# dcdc.net
KiCad netlist of a schematic drawn in EAGLE
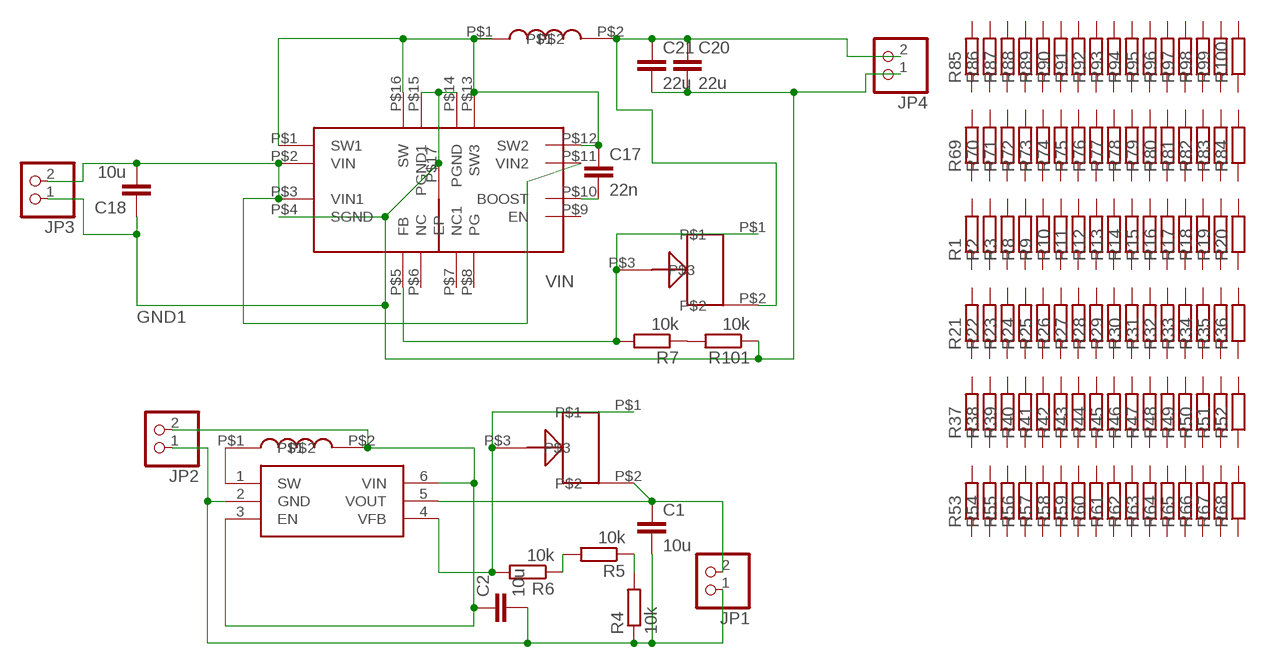
[diagram p0: schematic, sheet 1]

(export (version "E")
  (design (tool "Eeschema 10.0.6"))
  (components
    (comp (ref "C1")
      (value "10u")
      (footprint "eagle-import:C1206K")
      (libsource (lib "eagle-import") (part "C-EUC1206K"))
    )
    (comp (ref "C2")
      (value "10u")
      (footprint "eagle-import:C1206K")
      (libsource (lib "eagle-import") (part "C-EUC1206K"))
    )
    (comp (ref "C17")
      (value "22n")
      (footprint "eagle-import:C0603")
      (libsource (lib "eagle-import") (part "C-EUC0603"))
    )
    (comp (ref "C18")
      (value "10u")
      (footprint "eagle-import:C1206K")
      (libsource (lib "eagle-import") (part "C-EUC1206K"))
    )
    (comp (ref "C20")
      (value "22u")
      (footprint "eagle-import:C1206K")
      (libsource (lib "eagle-import") (part "C-EUC1206K"))
    )
    (comp (ref "C21")
      (value "22u")
      (footprint "eagle-import:C1206K")
      (libsource (lib "eagle-import") (part "C-EUC1206K"))
    )
    (comp (ref "JP1")
      (value "PINHD-1X2")
      (footprint "eagle-import:1X02")
      (libsource (lib "eagle-import") (part "PINHD-1X2"))
    )
    (comp (ref "JP2")
      (value "PINHD-1X2")
      (footprint "eagle-import:1X02")
      (libsource (lib "eagle-import") (part "PINHD-1X2"))
    )
    (comp (ref "JP3")
      (value "PINHD-1X2")
      (footprint "eagle-import:1X02")
      (libsource (lib "eagle-import") (part "PINHD-1X2"))
    )
    (comp (ref "JP4")
      (value "PINHD-1X2")
      (footprint "eagle-import:1X02")
      (libsource (lib "eagle-import") (part "PINHD-1X2"))
    )
    (comp (ref "R1")
      (value "R-EU_R0402")
      (footprint "eagle-import:R0402")
      (libsource (lib "eagle-import") (part "R-EU_R0402"))
    )
    (comp (ref "R2")
      (value "R-EU_R0402")
      (footprint "eagle-import:R0402")
      (libsource (lib "eagle-import") (part "R-EU_R0402"))
    )
    (comp (ref "R3")
      (value "R-EU_R0402")
      (footprint "eagle-import:R0402")
      (libsource (lib "eagle-import") (part "R-EU_R0402"))
    )
    (comp (ref "R4")
      (value "10k")
      (footprint "eagle-import:R0603")
      (libsource (lib "eagle-import") (part "R-EU_R0603"))
    )
    (comp (ref "R5")
      (value "10k")
      (footprint "eagle-import:R0603")
      (libsource (lib "eagle-import") (part "R-EU_R0603"))
    )
    (comp (ref "R6")
      (value "10k")
      (footprint "eagle-import:R0603")
      (libsource (lib "eagle-import") (part "R-EU_R0603"))
    )
    (comp (ref "R7")
      (value "10k")
      (footprint "eagle-import:R0603")
      (libsource (lib "eagle-import") (part "R-EU_R0603"))
    )
    (comp (ref "R8")
      (value "R-EU_R0402")
      (footprint "eagle-import:R0402")
      (libsource (lib "eagle-import") (part "R-EU_R0402"))
    )
    (comp (ref "R9")
      (value "R-EU_R0402")
      (footprint "eagle-import:R0402")
      (libsource (lib "eagle-import") (part "R-EU_R0402"))
    )
    (comp (ref "R10")
      (value "R-EU_R0402")
      (footprint "eagle-import:R0402")
      (libsource (lib "eagle-import") (part "R-EU_R0402"))
    )
    (comp (ref "R11")
      (value "R-EU_R0402")
      (footprint "eagle-import:R0402")
      (libsource (lib "eagle-import") (part "R-EU_R0402"))
    )
    (comp (ref "R12")
      (value "R-EU_R0402")
      (footprint "eagle-import:R0402")
      (libsource (lib "eagle-import") (part "R-EU_R0402"))
    )
    (comp (ref "R13")
      (value "R-EU_R0402")
      (footprint "eagle-import:R0402")
      (libsource (lib "eagle-import") (part "R-EU_R0402"))
    )
    (comp (ref "R14")
      (value "R-EU_R0402")
      (footprint "eagle-import:R0402")
      (libsource (lib "eagle-import") (part "R-EU_R0402"))
    )
    (comp (ref "R15")
      (value "R-EU_R0402")
      (footprint "eagle-import:R0402")
      (libsource (lib "eagle-import") (part "R-EU_R0402"))
    )
    (comp (ref "R16")
      (value "R-EU_R0402")
      (footprint "eagle-import:R0402")
      (libsource (lib "eagle-import") (part "R-EU_R0402"))
    )
    (comp (ref "R17")
      (value "R-EU_R0402")
      (footprint "eagle-import:R0402")
      (libsource (lib "eagle-import") (part "R-EU_R0402"))
    )
    (comp (ref "R18")
      (value "R-EU_R0402")
      (footprint "eagle-import:R0402")
      (libsource (lib "eagle-import") (part "R-EU_R0402"))
    )
    (comp (ref "R19")
      (value "R-EU_R0402")
      (footprint "eagle-import:R0402")
      (libsource (lib "eagle-import") (part "R-EU_R0402"))
    )
    (comp (ref "R20")
      (value "R-EU_R0402")
      (footprint "eagle-import:R0402")
      (libsource (lib "eagle-import") (part "R-EU_R0402"))
    )
    (comp (ref "R21")
      (value "R-EU_R0402")
      (footprint "eagle-import:R0402")
      (libsource (lib "eagle-import") (part "R-EU_R0402"))
    )
    (comp (ref "R22")
      (value "R-EU_R0402")
      (footprint "eagle-import:R0402")
      (libsource (lib "eagle-import") (part "R-EU_R0402"))
    )
    (comp (ref "R23")
      (value "R-EU_R0402")
      (footprint "eagle-import:R0402")
      (libsource (lib "eagle-import") (part "R-EU_R0402"))
    )
    (comp (ref "R24")
      (value "R-EU_R0402")
      (footprint "eagle-import:R0402")
      (libsource (lib "eagle-import") (part "R-EU_R0402"))
    )
    (comp (ref "R25")
      (value "R-EU_R0402")
      (footprint "eagle-import:R0402")
      (libsource (lib "eagle-import") (part "R-EU_R0402"))
    )
    (comp (ref "R26")
      (value "R-EU_R0402")
      (footprint "eagle-import:R0402")
      (libsource (lib "eagle-import") (part "R-EU_R0402"))
    )
    (comp (ref "R27")
      (value "R-EU_R0402")
      (footprint "eagle-import:R0402")
      (libsource (lib "eagle-import") (part "R-EU_R0402"))
    )
    (comp (ref "R28")
      (value "R-EU_R0402")
      (footprint "eagle-import:R0402")
      (libsource (lib "eagle-import") (part "R-EU_R0402"))
    )
    (comp (ref "R29")
      (value "R-EU_R0402")
      (footprint "eagle-import:R0402")
      (libsource (lib "eagle-import") (part "R-EU_R0402"))
    )
    (comp (ref "R30")
      (value "R-EU_R0402")
      (footprint "eagle-import:R0402")
      (libsource (lib "eagle-import") (part "R-EU_R0402"))
    )
    (comp (ref "R31")
      (value "R-EU_R0402")
      (footprint "eagle-import:R0402")
      (libsource (lib "eagle-import") (part "R-EU_R0402"))
    )
    (comp (ref "R32")
      (value "R-EU_R0402")
      (footprint "eagle-import:R0402")
      (libsource (lib "eagle-import") (part "R-EU_R0402"))
    )
    (comp (ref "R33")
      (value "R-EU_R0402")
      (footprint "eagle-import:R0402")
      (libsource (lib "eagle-import") (part "R-EU_R0402"))
    )
    (comp (ref "R34")
      (value "R-EU_R0402")
      (footprint "eagle-import:R0402")
      (libsource (lib "eagle-import") (part "R-EU_R0402"))
    )
    (comp (ref "R35")
      (value "R-EU_R0402")
      (footprint "eagle-import:R0402")
      (libsource (lib "eagle-import") (part "R-EU_R0402"))
    )
    (comp (ref "R36")
      (value "R-EU_R0402")
      (footprint "eagle-import:R0402")
      (libsource (lib "eagle-import") (part "R-EU_R0402"))
    )
    (comp (ref "R37")
      (value "R-EU_R0603")
      (footprint "eagle-import:R0603")
      (libsource (lib "eagle-import") (part "R-EU_R0603"))
    )
    (comp (ref "R38")
      (value "R-EU_R0603")
      (footprint "eagle-import:R0603")
      (libsource (lib "eagle-import") (part "R-EU_R0603"))
    )
    (comp (ref "R39")
      (value "R-EU_R0603")
      (footprint "eagle-import:R0603")
      (libsource (lib "eagle-import") (part "R-EU_R0603"))
    )
    (comp (ref "R40")
      (value "R-EU_R0603")
      (footprint "eagle-import:R0603")
      (libsource (lib "eagle-import") (part "R-EU_R0603"))
    )
    (comp (ref "R41")
      (value "R-EU_R0603")
      (footprint "eagle-import:R0603")
      (libsource (lib "eagle-import") (part "R-EU_R0603"))
    )
    (comp (ref "R42")
      (value "R-EU_R0603")
      (footprint "eagle-import:R0603")
      (libsource (lib "eagle-import") (part "R-EU_R0603"))
    )
    (comp (ref "R43")
      (value "R-EU_R0603")
      (footprint "eagle-import:R0603")
      (libsource (lib "eagle-import") (part "R-EU_R0603"))
    )
    (comp (ref "R44")
      (value "R-EU_R0603")
      (footprint "eagle-import:R0603")
      (libsource (lib "eagle-import") (part "R-EU_R0603"))
    )
    (comp (ref "R45")
      (value "R-EU_R0603")
      (footprint "eagle-import:R0603")
      (libsource (lib "eagle-import") (part "R-EU_R0603"))
    )
    (comp (ref "R46")
      (value "R-EU_R0603")
      (footprint "eagle-import:R0603")
      (libsource (lib "eagle-import") (part "R-EU_R0603"))
    )
    (comp (ref "R47")
      (value "R-EU_R0603")
      (footprint "eagle-import:R0603")
      (libsource (lib "eagle-import") (part "R-EU_R0603"))
    )
    (comp (ref "R48")
      (value "R-EU_R0603")
      (footprint "eagle-import:R0603")
      (libsource (lib "eagle-import") (part "R-EU_R0603"))
    )
    (comp (ref "R49")
      (value "R-EU_R0603")
      (footprint "eagle-import:R0603")
      (libsource (lib "eagle-import") (part "R-EU_R0603"))
    )
    (comp (ref "R50")
      (value "R-EU_R0603")
      (footprint "eagle-import:R0603")
      (libsource (lib "eagle-import") (part "R-EU_R0603"))
    )
    (comp (ref "R51")
      (value "R-EU_R0603")
      (footprint "eagle-import:R0603")
      (libsource (lib "eagle-import") (part "R-EU_R0603"))
    )
    (comp (ref "R52")
      (value "R-EU_R0603")
      (footprint "eagle-import:R0603")
      (libsource (lib "eagle-import") (part "R-EU_R0603"))
    )
    (comp (ref "R53")
      (value "R-EU_R0603")
      (footprint "eagle-import:R0603")
      (libsource (lib "eagle-import") (part "R-EU_R0603"))
    )
    (comp (ref "R54")
      (value "R-EU_R0603")
      (footprint "eagle-import:R0603")
      (libsource (lib "eagle-import") (part "R-EU_R0603"))
    )
    (comp (ref "R55")
      (value "R-EU_R0603")
      (footprint "eagle-import:R0603")
      (libsource (lib "eagle-import") (part "R-EU_R0603"))
    )
    (comp (ref "R56")
      (value "R-EU_R0603")
      (footprint "eagle-import:R0603")
      (libsource (lib "eagle-import") (part "R-EU_R0603"))
    )
    (comp (ref "R57")
      (value "R-EU_R0603")
      (footprint "eagle-import:R0603")
      (libsource (lib "eagle-import") (part "R-EU_R0603"))
    )
    (comp (ref "R58")
      (value "R-EU_R0603")
      (footprint "eagle-import:R0603")
      (libsource (lib "eagle-import") (part "R-EU_R0603"))
    )
    (comp (ref "R59")
      (value "R-EU_R0603")
      (footprint "eagle-import:R0603")
      (libsource (lib "eagle-import") (part "R-EU_R0603"))
    )
    (comp (ref "R60")
      (value "R-EU_R0603")
      (footprint "eagle-import:R0603")
      (libsource (lib "eagle-import") (part "R-EU_R0603"))
    )
    (comp (ref "R61")
      (value "R-EU_R0603")
      (footprint "eagle-import:R0603")
      (libsource (lib "eagle-import") (part "R-EU_R0603"))
    )
    (comp (ref "R62")
      (value "R-EU_R0603")
      (footprint "eagle-import:R0603")
      (libsource (lib "eagle-import") (part "R-EU_R0603"))
    )
    (comp (ref "R63")
      (value "R-EU_R0603")
      (footprint "eagle-import:R0603")
      (libsource (lib "eagle-import") (part "R-EU_R0603"))
    )
    (comp (ref "R64")
      (value "R-EU_R0603")
      (footprint "eagle-import:R0603")
      (libsource (lib "eagle-import") (part "R-EU_R0603"))
    )
    (comp (ref "R65")
      (value "R-EU_R0603")
      (footprint "eagle-import:R0603")
      (libsource (lib "eagle-import") (part "R-EU_R0603"))
    )
    (comp (ref "R66")
      (value "R-EU_R0603")
      (footprint "eagle-import:R0603")
      (libsource (lib "eagle-import") (part "R-EU_R0603"))
    )
    (comp (ref "R67")
      (value "R-EU_R0603")
      (footprint "eagle-import:R0603")
      (libsource (lib "eagle-import") (part "R-EU_R0603"))
    )
    (comp (ref "R68")
      (value "R-EU_R0603")
      (footprint "eagle-import:R0603")
      (libsource (lib "eagle-import") (part "R-EU_R0603"))
    )
    (comp (ref "R69")
      (value "R-EU_R0402")
      (footprint "eagle-import:R0402")
      (libsource (lib "eagle-import") (part "R-EU_R0402"))
    )
    (comp (ref "R70")
      (value "R-EU_R0402")
      (footprint "eagle-import:R0402")
      (libsource (lib "eagle-import") (part "R-EU_R0402"))
    )
    (comp (ref "R71")
      (value "R-EU_R0402")
      (footprint "eagle-import:R0402")
      (libsource (lib "eagle-import") (part "R-EU_R0402"))
    )
    (comp (ref "R72")
      (value "R-EU_R0402")
      (footprint "eagle-import:R0402")
      (libsource (lib "eagle-import") (part "R-EU_R0402"))
    )
    (comp (ref "R73")
      (value "R-EU_R0402")
      (footprint "eagle-import:R0402")
      (libsource (lib "eagle-import") (part "R-EU_R0402"))
    )
    (comp (ref "R74")
      (value "R-EU_R0402")
      (footprint "eagle-import:R0402")
      (libsource (lib "eagle-import") (part "R-EU_R0402"))
    )
    (comp (ref "R75")
      (value "R-EU_R0402")
      (footprint "eagle-import:R0402")
      (libsource (lib "eagle-import") (part "R-EU_R0402"))
    )
    (comp (ref "R76")
      (value "R-EU_R0402")
      (footprint "eagle-import:R0402")
      (libsource (lib "eagle-import") (part "R-EU_R0402"))
    )
    (comp (ref "R77")
      (value "R-EU_R0402")
      (footprint "eagle-import:R0402")
      (libsource (lib "eagle-import") (part "R-EU_R0402"))
    )
    (comp (ref "R78")
      (value "R-EU_R0402")
      (footprint "eagle-import:R0402")
      (libsource (lib "eagle-import") (part "R-EU_R0402"))
    )
    (comp (ref "R79")
      (value "R-EU_R0402")
      (footprint "eagle-import:R0402")
      (libsource (lib "eagle-import") (part "R-EU_R0402"))
    )
    (comp (ref "R80")
      (value "R-EU_R0402")
      (footprint "eagle-import:R0402")
      (libsource (lib "eagle-import") (part "R-EU_R0402"))
    )
    (comp (ref "R81")
      (value "R-EU_R0402")
      (footprint "eagle-import:R0402")
      (libsource (lib "eagle-import") (part "R-EU_R0402"))
    )
    (comp (ref "R82")
      (value "R-EU_R0402")
      (footprint "eagle-import:R0402")
      (libsource (lib "eagle-import") (part "R-EU_R0402"))
    )
    (comp (ref "R83")
      (value "R-EU_R0402")
      (footprint "eagle-import:R0402")
      (libsource (lib "eagle-import") (part "R-EU_R0402"))
    )
    (comp (ref "R84")
      (value "R-EU_R0402")
      (footprint "eagle-import:R0402")
      (libsource (lib "eagle-import") (part "R-EU_R0402"))
    )
    (comp (ref "R85")
      (value "R-EU_R0402")
      (footprint "eagle-import:R0402")
      (libsource (lib "eagle-import") (part "R-EU_R0402"))
    )
    (comp (ref "R86")
      (value "R-EU_R0402")
      (footprint "eagle-import:R0402")
      (libsource (lib "eagle-import") (part "R-EU_R0402"))
    )
    (comp (ref "R87")
      (value "R-EU_R0402")
      (footprint "eagle-import:R0402")
      (libsource (lib "eagle-import") (part "R-EU_R0402"))
    )
    (comp (ref "R88")
      (value "R-EU_R0402")
      (footprint "eagle-import:R0402")
      (libsource (lib "eagle-import") (part "R-EU_R0402"))
    )
    (comp (ref "R89")
      (value "R-EU_R0402")
      (footprint "eagle-import:R0402")
      (libsource (lib "eagle-import") (part "R-EU_R0402"))
    )
    (comp (ref "R90")
      (value "R-EU_R0402")
      (footprint "eagle-import:R0402")
      (libsource (lib "eagle-import") (part "R-EU_R0402"))
    )
    (comp (ref "R91")
      (value "R-EU_R0402")
      (footprint "eagle-import:R0402")
      (libsource (lib "eagle-import") (part "R-EU_R0402"))
    )
    (comp (ref "R92")
      (value "R-EU_R0402")
      (footprint "eagle-import:R0402")
      (libsource (lib "eagle-import") (part "R-EU_R0402"))
    )
    (comp (ref "R93")
      (value "R-EU_R0402")
      (footprint "eagle-import:R0402")
      (libsource (lib "eagle-import") (part "R-EU_R0402"))
    )
    (comp (ref "R94")
      (value "R-EU_R0402")
      (footprint "eagle-import:R0402")
      (libsource (lib "eagle-import") (part "R-EU_R0402"))
    )
    (comp (ref "R95")
      (value "R-EU_R0402")
      (footprint "eagle-import:R0402")
      (libsource (lib "eagle-import") (part "R-EU_R0402"))
    )
    (comp (ref "R96")
      (value "R-EU_R0402")
      (footprint "eagle-import:R0402")
      (libsource (lib "eagle-import") (part "R-EU_R0402"))
    )
    (comp (ref "R97")
      (value "R-EU_R0402")
      (footprint "eagle-import:R0402")
      (libsource (lib "eagle-import") (part "R-EU_R0402"))
    )
    (comp (ref "R98")
      (value "R-EU_R0402")
      (footprint "eagle-import:R0402")
      (libsource (lib "eagle-import") (part "R-EU_R0402"))
    )
    (comp (ref "R99")
      (value "R-EU_R0402")
      (footprint "eagle-import:R0402")
      (libsource (lib "eagle-import") (part "R-EU_R0402"))
    )
    (comp (ref "R100")
      (value "R-EU_R0402")
      (footprint "eagle-import:R0402")
      (libsource (lib "eagle-import") (part "R-EU_R0402"))
    )
    (comp (ref "R101")
      (value "10k")
      (footprint "eagle-import:R0603")
      (libsource (lib "eagle-import") (part "R-EU_R0603"))
    )
    (comp (ref "U$1")
      (value "TRIMMER3MM")
      (footprint "eagle-import:TRIMMER3MM")
      (libsource (lib "eagle-import") (part "TRIMMER3MM"))
    )
    (comp (ref "U$2")
      (value "MCP1640SOT23-6")
      (footprint "eagle-import:SOT23-6L")
      (libsource (lib "eagle-import") (part "MCP1640SOT23-6"))
    )
    (comp (ref "U$3")
      (value "EPL2014")
      (footprint "eagle-import:EPL2014")
      (libsource (lib "eagle-import") (part "EPL2014"))
    )
    (comp (ref "U$4")
      (value "TRIMMER3MM")
      (footprint "eagle-import:TRIMMER3MM")
      (libsource (lib "eagle-import") (part "TRIMMER3MM"))
    )
    (comp (ref "U$18")
      (value "NR6028")
      (footprint "eagle-import:NRS6")
      (libsource (lib "eagle-import") (part "NR6028"))
    )
    (comp (ref "U$19")
      (value "MCP16323")
      (footprint "eagle-import:QFN16")
      (libsource (lib "eagle-import") (part "MCP16323"))
    )
  )
  (nets
    (net (code "1") (name "/GND1") (class "Default")
      (node (ref "C18") (pin "1") (pinfunction "1_1") (pintype "passive"))
      (node (ref "C20") (pin "2") (pinfunction "2_2") (pintype "passive"))
      (node (ref "C21") (pin "2") (pinfunction "2_2") (pintype "passive"))
      (node (ref "JP3") (pin "1") (pinfunction "1_1") (pintype "passive"))
      (node (ref "JP4") (pin "1") (pinfunction "1_1") (pintype "passive"))
      (node (ref "R101") (pin "1") (pinfunction "1_1") (pintype "passive"))
      (node (ref "U$19") (pin "P$14") (pinfunction "PGND_P$14") (pintype "bidirectional"))
      (node (ref "U$19") (pin "P$15") (pinfunction "PGND1_P$15") (pintype "bidirectional"))
      (node (ref "U$19") (pin "P$17") (pinfunction "EP_P$17") (pintype "bidirectional"))
      (node (ref "U$19") (pin "P$4") (pinfunction "SGND_P$4") (pintype "bidirectional"))
    )
    (net (code "2") (name "/VIN") (class "Default")
      (node (ref "C18") (pin "2") (pinfunction "2_2") (pintype "passive"))
      (node (ref "JP3") (pin "2") (pinfunction "2_2") (pintype "passive"))
      (node (ref "U$19") (pin "P$11") (pinfunction "VIN2_P$11") (pintype "bidirectional"))
      (node (ref "U$19") (pin "P$2") (pinfunction "VIN_P$2") (pintype "bidirectional"))
      (node (ref "U$19") (pin "P$3") (pinfunction "VIN1_P$3") (pintype "bidirectional"))
    )
    (net (code "3") (name "Net-(C20-Pad1)") (class "Default")
      (node (ref "C20") (pin "1") (pinfunction "1_1") (pintype "passive"))
      (node (ref "C21") (pin "1") (pinfunction "1_1") (pintype "passive"))
      (node (ref "JP4") (pin "2") (pinfunction "2_2") (pintype "passive"))
      (node (ref "U$18") (pin "P$2") (pinfunction "P$2_P$2") (pintype "bidirectional"))
      (node (ref "U$4") (pin "P$2") (pinfunction "P$2_P$2") (pintype "bidirectional"))
    )
    (net (code "4") (name "Net-(R4-Pad2)") (class "Default")
      (node (ref "R4") (pin "2") (pinfunction "2_2") (pintype "passive"))
      (node (ref "R5") (pin "1") (pinfunction "1_1") (pintype "passive"))
    )
    (net (code "5") (name "Net-(R5-Pad2)") (class "Default")
      (node (ref "R5") (pin "2") (pinfunction "2_2") (pintype "passive"))
      (node (ref "R6") (pin "1") (pinfunction "1_1") (pintype "passive"))
    )
    (net (code "6") (name "Net-(R101-Pad2)") (class "Default")
      (node (ref "R101") (pin "2") (pinfunction "2_2") (pintype "passive"))
      (node (ref "R7") (pin "1") (pinfunction "1_1") (pintype "passive"))
    )
    (net (code "7") (name "Net-(U$2-EN)") (class "Default")
      (node (ref "C2") (pin "1") (pinfunction "1_1") (pintype "passive"))
      (node (ref "JP2") (pin "2") (pinfunction "2_2") (pintype "passive"))
      (node (ref "U$2") (pin "3") (pinfunction "EN_3") (pintype "bidirectional"))
      (node (ref "U$2") (pin "6") (pinfunction "VIN_6") (pintype "bidirectional"))
      (node (ref "U$3") (pin "P$2") (pinfunction "P$2_P$2") (pintype "bidirectional"))
    )
    (net (code "8") (name "Net-(U$2-GND)") (class "Default")
      (node (ref "C1") (pin "2") (pinfunction "2_2") (pintype "passive"))
      (node (ref "C2") (pin "2") (pinfunction "2_2") (pintype "passive"))
      (node (ref "JP1") (pin "1") (pinfunction "1_1") (pintype "passive"))
      (node (ref "JP2") (pin "1") (pinfunction "1_1") (pintype "passive"))
      (node (ref "R4") (pin "1") (pinfunction "1_1") (pintype "passive"))
      (node (ref "U$2") (pin "2") (pinfunction "GND_2") (pintype "bidirectional"))
    )
    (net (code "9") (name "Net-(U$2-SW)") (class "Default")
      (node (ref "U$2") (pin "1") (pinfunction "SW_1") (pintype "bidirectional"))
      (node (ref "U$3") (pin "P$1") (pinfunction "P$1_P$1") (pintype "bidirectional"))
    )
    (net (code "10") (name "Net-(U$2-VFB)") (class "Default")
      (node (ref "R6") (pin "2") (pinfunction "2_2") (pintype "passive"))
      (node (ref "U$1") (pin "P$1") (pinfunction "P$1_P$1") (pintype "bidirectional"))
      (node (ref "U$1") (pin "P$3") (pinfunction "P$3_P$3") (pintype "bidirectional"))
      (node (ref "U$2") (pin "4") (pinfunction "VFB_4") (pintype "bidirectional"))
    )
    (net (code "11") (name "Net-(U$2-VOUT)") (class "Default")
      (node (ref "C1") (pin "1") (pinfunction "1_1") (pintype "passive"))
      (node (ref "JP1") (pin "2") (pinfunction "2_2") (pintype "passive"))
      (node (ref "U$1") (pin "P$2") (pinfunction "P$2_P$2") (pintype "bidirectional"))
      (node (ref "U$2") (pin "5") (pinfunction "VOUT_5") (pintype "bidirectional"))
    )
    (net (code "12") (name "Net-(U$19-BOOST)") (class "Default")
      (node (ref "C17") (pin "2") (pinfunction "2_2") (pintype "passive"))
      (node (ref "U$19") (pin "P$10") (pinfunction "BOOST_P$10") (pintype "bidirectional"))
    )
    (net (code "13") (name "Net-(U$19-FB)") (class "Default")
      (node (ref "R7") (pin "2") (pinfunction "2_2") (pintype "passive"))
      (node (ref "U$19") (pin "P$5") (pinfunction "FB_P$5") (pintype "bidirectional"))
      (node (ref "U$4") (pin "P$1") (pinfunction "P$1_P$1") (pintype "bidirectional"))
      (node (ref "U$4") (pin "P$3") (pinfunction "P$3_P$3") (pintype "bidirectional"))
    )
    (net (code "14") (name "Net-(U$19-SW)") (class "Default")
      (node (ref "C17") (pin "1") (pinfunction "1_1") (pintype "passive"))
      (node (ref "U$18") (pin "P$1") (pinfunction "P$1_P$1") (pintype "bidirectional"))
      (node (ref "U$19") (pin "P$1") (pinfunction "SW1_P$1") (pintype "bidirectional"))
      (node (ref "U$19") (pin "P$12") (pinfunction "SW2_P$12") (pintype "bidirectional"))
      (node (ref "U$19") (pin "P$13") (pinfunction "SW3_P$13") (pintype "bidirectional"))
      (node (ref "U$19") (pin "P$16") (pinfunction "SW_P$16") (pintype "bidirectional"))
    )
    (net (code "15") (name "unconnected-(R1-Pad1)") (class "Default")
      (node (ref "R1") (pin "1") (pinfunction "1_1") (pintype "passive"))
    )
    (net (code "16") (name "unconnected-(R1-Pad2)") (class "Default")
      (node (ref "R1") (pin "2") (pinfunction "2_2") (pintype "passive"))
    )
    (net (code "17") (name "unconnected-(R2-Pad1)") (class "Default")
      (node (ref "R2") (pin "1") (pinfunction "1_1") (pintype "passive"))
    )
    (net (code "18") (name "unconnected-(R2-Pad2)") (class "Default")
      (node (ref "R2") (pin "2") (pinfunction "2_2") (pintype "passive"))
    )
    (net (code "19") (name "unconnected-(R3-Pad1)") (class "Default")
      (node (ref "R3") (pin "1") (pinfunction "1_1") (pintype "passive"))
    )
    (net (code "20") (name "unconnected-(R3-Pad2)") (class "Default")
      (node (ref "R3") (pin "2") (pinfunction "2_2") (pintype "passive"))
    )
    (net (code "21") (name "unconnected-(R8-Pad1)") (class "Default")
      (node (ref "R8") (pin "1") (pinfunction "1_1") (pintype "passive"))
    )
    (net (code "22") (name "unconnected-(R8-Pad2)") (class "Default")
      (node (ref "R8") (pin "2") (pinfunction "2_2") (pintype "passive"))
    )
    (net (code "23") (name "unconnected-(R9-Pad1)") (class "Default")
      (node (ref "R9") (pin "1") (pinfunction "1_1") (pintype "passive"))
    )
    (net (code "24") (name "unconnected-(R9-Pad2)") (class "Default")
      (node (ref "R9") (pin "2") (pinfunction "2_2") (pintype "passive"))
    )
    (net (code "25") (name "unconnected-(R10-Pad1)") (class "Default")
      (node (ref "R10") (pin "1") (pinfunction "1_1") (pintype "passive"))
    )
    (net (code "26") (name "unconnected-(R10-Pad2)") (class "Default")
      (node (ref "R10") (pin "2") (pinfunction "2_2") (pintype "passive"))
    )
    (net (code "27") (name "unconnected-(R11-Pad1)") (class "Default")
      (node (ref "R11") (pin "1") (pinfunction "1_1") (pintype "passive"))
    )
    (net (code "28") (name "unconnected-(R11-Pad2)") (class "Default")
      (node (ref "R11") (pin "2") (pinfunction "2_2") (pintype "passive"))
    )
    (net (code "29") (name "unconnected-(R12-Pad1)") (class "Default")
      (node (ref "R12") (pin "1") (pinfunction "1_1") (pintype "passive"))
    )
    (net (code "30") (name "unconnected-(R12-Pad2)") (class "Default")
      (node (ref "R12") (pin "2") (pinfunction "2_2") (pintype "passive"))
    )
    (net (code "31") (name "unconnected-(R13-Pad1)") (class "Default")
      (node (ref "R13") (pin "1") (pinfunction "1_1") (pintype "passive"))
    )
    (net (code "32") (name "unconnected-(R13-Pad2)") (class "Default")
      (node (ref "R13") (pin "2") (pinfunction "2_2") (pintype "passive"))
    )
    (net (code "33") (name "unconnected-(R14-Pad1)") (class "Default")
      (node (ref "R14") (pin "1") (pinfunction "1_1") (pintype "passive"))
    )
    (net (code "34") (name "unconnected-(R14-Pad2)") (class "Default")
      (node (ref "R14") (pin "2") (pinfunction "2_2") (pintype "passive"))
    )
    (net (code "35") (name "unconnected-(R15-Pad1)") (class "Default")
      (node (ref "R15") (pin "1") (pinfunction "1_1") (pintype "passive"))
    )
    (net (code "36") (name "unconnected-(R15-Pad2)") (class "Default")
      (node (ref "R15") (pin "2") (pinfunction "2_2") (pintype "passive"))
    )
    (net (code "37") (name "unconnected-(R16-Pad1)") (class "Default")
      (node (ref "R16") (pin "1") (pinfunction "1_1") (pintype "passive"))
    )
    (net (code "38") (name "unconnected-(R16-Pad2)") (class "Default")
      (node (ref "R16") (pin "2") (pinfunction "2_2") (pintype "passive"))
    )
    (net (code "39") (name "unconnected-(R17-Pad1)") (class "Default")
      (node (ref "R17") (pin "1") (pinfunction "1_1") (pintype "passive"))
    )
    (net (code "40") (name "unconnected-(R17-Pad2)") (class "Default")
      (node (ref "R17") (pin "2") (pinfunction "2_2") (pintype "passive"))
    )
    (net (code "41") (name "unconnected-(R18-Pad1)") (class "Default")
      (node (ref "R18") (pin "1") (pinfunction "1_1") (pintype "passive"))
    )
    (net (code "42") (name "unconnected-(R18-Pad2)") (class "Default")
      (node (ref "R18") (pin "2") (pinfunction "2_2") (pintype "passive"))
    )
    (net (code "43") (name "unconnected-(R19-Pad1)") (class "Default")
      (node (ref "R19") (pin "1") (pinfunction "1_1") (pintype "passive"))
    )
    (net (code "44") (name "unconnected-(R19-Pad2)") (class "Default")
      (node (ref "R19") (pin "2") (pinfunction "2_2") (pintype "passive"))
    )
    (net (code "45") (name "unconnected-(R20-Pad1)") (class "Default")
      (node (ref "R20") (pin "1") (pinfunction "1_1") (pintype "passive"))
    )
    (net (code "46") (name "unconnected-(R20-Pad2)") (class "Default")
      (node (ref "R20") (pin "2") (pinfunction "2_2") (pintype "passive"))
    )
    (net (code "47") (name "unconnected-(R21-Pad1)") (class "Default")
      (node (ref "R21") (pin "1") (pinfunction "1_1") (pintype "passive"))
    )
    (net (code "48") (name "unconnected-(R21-Pad2)") (class "Default")
      (node (ref "R21") (pin "2") (pinfunction "2_2") (pintype "passive"))
    )
    (net (code "49") (name "unconnected-(R22-Pad1)") (class "Default")
      (node (ref "R22") (pin "1") (pinfunction "1_1") (pintype "passive"))
    )
    (net (code "50") (name "unconnected-(R22-Pad2)") (class "Default")
      (node (ref "R22") (pin "2") (pinfunction "2_2") (pintype "passive"))
    )
    (net (code "51") (name "unconnected-(R23-Pad1)") (class "Default")
      (node (ref "R23") (pin "1") (pinfunction "1_1") (pintype "passive"))
    )
    (net (code "52") (name "unconnected-(R23-Pad2)") (class "Default")
      (node (ref "R23") (pin "2") (pinfunction "2_2") (pintype "passive"))
    )
    (net (code "53") (name "unconnected-(R24-Pad1)") (class "Default")
      (node (ref "R24") (pin "1") (pinfunction "1_1") (pintype "passive"))
    )
    (net (code "54") (name "unconnected-(R24-Pad2)") (class "Default")
      (node (ref "R24") (pin "2") (pinfunction "2_2") (pintype "passive"))
    )
    (net (code "55") (name "unconnected-(R25-Pad1)") (class "Default")
      (node (ref "R25") (pin "1") (pinfunction "1_1") (pintype "passive"))
    )
    (net (code "56") (name "unconnected-(R25-Pad2)") (class "Default")
      (node (ref "R25") (pin "2") (pinfunction "2_2") (pintype "passive"))
    )
    (net (code "57") (name "unconnected-(R26-Pad1)") (class "Default")
      (node (ref "R26") (pin "1") (pinfunction "1_1") (pintype "passive"))
    )
    (net (code "58") (name "unconnected-(R26-Pad2)") (class "Default")
      (node (ref "R26") (pin "2") (pinfunction "2_2") (pintype "passive"))
    )
    (net (code "59") (name "unconnected-(R27-Pad1)") (class "Default")
      (node (ref "R27") (pin "1") (pinfunction "1_1") (pintype "passive"))
    )
    (net (code "60") (name "unconnected-(R27-Pad2)") (class "Default")
      (node (ref "R27") (pin "2") (pinfunction "2_2") (pintype "passive"))
    )
    (net (code "61") (name "unconnected-(R28-Pad1)") (class "Default")
      (node (ref "R28") (pin "1") (pinfunction "1_1") (pintype "passive"))
    )
    (net (code "62") (name "unconnected-(R28-Pad2)") (class "Default")
      (node (ref "R28") (pin "2") (pinfunction "2_2") (pintype "passive"))
    )
    (net (code "63") (name "unconnected-(R29-Pad1)") (class "Default")
      (node (ref "R29") (pin "1") (pinfunction "1_1") (pintype "passive"))
    )
    (net (code "64") (name "unconnected-(R29-Pad2)") (class "Default")
      (node (ref "R29") (pin "2") (pinfunction "2_2") (pintype "passive"))
    )
    (net (code "65") (name "unconnected-(R30-Pad1)") (class "Default")
      (node (ref "R30") (pin "1") (pinfunction "1_1") (pintype "passive"))
    )
    (net (code "66") (name "unconnected-(R30-Pad2)") (class "Default")
      (node (ref "R30") (pin "2") (pinfunction "2_2") (pintype "passive"))
    )
    (net (code "67") (name "unconnected-(R31-Pad1)") (class "Default")
      (node (ref "R31") (pin "1") (pinfunction "1_1") (pintype "passive"))
    )
    (net (code "68") (name "unconnected-(R31-Pad2)") (class "Default")
      (node (ref "R31") (pin "2") (pinfunction "2_2") (pintype "passive"))
    )
    (net (code "69") (name "unconnected-(R32-Pad1)") (class "Default")
      (node (ref "R32") (pin "1") (pinfunction "1_1") (pintype "passive"))
    )
    (net (code "70") (name "unconnected-(R32-Pad2)") (class "Default")
      (node (ref "R32") (pin "2") (pinfunction "2_2") (pintype "passive"))
    )
    (net (code "71") (name "unconnected-(R33-Pad1)") (class "Default")
      (node (ref "R33") (pin "1") (pinfunction "1_1") (pintype "passive"))
    )
    (net (code "72") (name "unconnected-(R33-Pad2)") (class "Default")
      (node (ref "R33") (pin "2") (pinfunction "2_2") (pintype "passive"))
    )
    (net (code "73") (name "unconnected-(R34-Pad1)") (class "Default")
      (node (ref "R34") (pin "1") (pinfunction "1_1") (pintype "passive"))
    )
    (net (code "74") (name "unconnected-(R34-Pad2)") (class "Default")
      (node (ref "R34") (pin "2") (pinfunction "2_2") (pintype "passive"))
    )
    (net (code "75") (name "unconnected-(R35-Pad1)") (class "Default")
      (node (ref "R35") (pin "1") (pinfunction "1_1") (pintype "passive"))
    )
    (net (code "76") (name "unconnected-(R35-Pad2)") (class "Default")
      (node (ref "R35") (pin "2") (pinfunction "2_2") (pintype "passive"))
    )
    (net (code "77") (name "unconnected-(R36-Pad1)") (class "Default")
      (node (ref "R36") (pin "1") (pinfunction "1_1") (pintype "passive"))
    )
    (net (code "78") (name "unconnected-(R36-Pad2)") (class "Default")
      (node (ref "R36") (pin "2") (pinfunction "2_2") (pintype "passive"))
    )
    (net (code "79") (name "unconnected-(R37-Pad1)") (class "Default")
      (node (ref "R37") (pin "1") (pinfunction "1_1") (pintype "passive"))
    )
    (net (code "80") (name "unconnected-(R37-Pad2)") (class "Default")
      (node (ref "R37") (pin "2") (pinfunction "2_2") (pintype "passive"))
    )
    (net (code "81") (name "unconnected-(R38-Pad1)") (class "Default")
      (node (ref "R38") (pin "1") (pinfunction "1_1") (pintype "passive"))
    )
    (net (code "82") (name "unconnected-(R38-Pad2)") (class "Default")
      (node (ref "R38") (pin "2") (pinfunction "2_2") (pintype "passive"))
    )
    (net (code "83") (name "unconnected-(R39-Pad1)") (class "Default")
      (node (ref "R39") (pin "1") (pinfunction "1_1") (pintype "passive"))
    )
    (net (code "84") (name "unconnected-(R39-Pad2)") (class "Default")
      (node (ref "R39") (pin "2") (pinfunction "2_2") (pintype "passive"))
    )
    (net (code "85") (name "unconnected-(R40-Pad1)") (class "Default")
      (node (ref "R40") (pin "1") (pinfunction "1_1") (pintype "passive"))
    )
    (net (code "86") (name "unconnected-(R40-Pad2)") (class "Default")
      (node (ref "R40") (pin "2") (pinfunction "2_2") (pintype "passive"))
    )
    (net (code "87") (name "unconnected-(R41-Pad1)") (class "Default")
      (node (ref "R41") (pin "1") (pinfunction "1_1") (pintype "passive"))
    )
    (net (code "88") (name "unconnected-(R41-Pad2)") (class "Default")
      (node (ref "R41") (pin "2") (pinfunction "2_2") (pintype "passive"))
    )
    (net (code "89") (name "unconnected-(R42-Pad1)") (class "Default")
      (node (ref "R42") (pin "1") (pinfunction "1_1") (pintype "passive"))
    )
    (net (code "90") (name "unconnected-(R42-Pad2)") (class "Default")
      (node (ref "R42") (pin "2") (pinfunction "2_2") (pintype "passive"))
    )
    (net (code "91") (name "unconnected-(R43-Pad1)") (class "Default")
      (node (ref "R43") (pin "1") (pinfunction "1_1") (pintype "passive"))
    )
    (net (code "92") (name "unconnected-(R43-Pad2)") (class "Default")
      (node (ref "R43") (pin "2") (pinfunction "2_2") (pintype "passive"))
    )
    (net (code "93") (name "unconnected-(R44-Pad1)") (class "Default")
      (node (ref "R44") (pin "1") (pinfunction "1_1") (pintype "passive"))
    )
    (net (code "94") (name "unconnected-(R44-Pad2)") (class "Default")
      (node (ref "R44") (pin "2") (pinfunction "2_2") (pintype "passive"))
    )
    (net (code "95") (name "unconnected-(R45-Pad1)") (class "Default")
      (node (ref "R45") (pin "1") (pinfunction "1_1") (pintype "passive"))
    )
    (net (code "96") (name "unconnected-(R45-Pad2)") (class "Default")
      (node (ref "R45") (pin "2") (pinfunction "2_2") (pintype "passive"))
    )
    (net (code "97") (name "unconnected-(R46-Pad1)") (class "Default")
      (node (ref "R46") (pin "1") (pinfunction "1_1") (pintype "passive"))
    )
    (net (code "98") (name "unconnected-(R46-Pad2)") (class "Default")
      (node (ref "R46") (pin "2") (pinfunction "2_2") (pintype "passive"))
    )
    (net (code "99") (name "unconnected-(R47-Pad1)") (class "Default")
      (node (ref "R47") (pin "1") (pinfunction "1_1") (pintype "passive"))
    )
    (net (code "100") (name "unconnected-(R47-Pad2)") (class "Default")
      (node (ref "R47") (pin "2") (pinfunction "2_2") (pintype "passive"))
    )
    (net (code "101") (name "unconnected-(R48-Pad1)") (class "Default")
      (node (ref "R48") (pin "1") (pinfunction "1_1") (pintype "passive"))
    )
    (net (code "102") (name "unconnected-(R48-Pad2)") (class "Default")
      (node (ref "R48") (pin "2") (pinfunction "2_2") (pintype "passive"))
    )
    (net (code "103") (name "unconnected-(R49-Pad1)") (class "Default")
      (node (ref "R49") (pin "1") (pinfunction "1_1") (pintype "passive"))
    )
    (net (code "104") (name "unconnected-(R49-Pad2)") (class "Default")
      (node (ref "R49") (pin "2") (pinfunction "2_2") (pintype "passive"))
    )
    (net (code "105") (name "unconnected-(R50-Pad1)") (class "Default")
      (node (ref "R50") (pin "1") (pinfunction "1_1") (pintype "passive"))
    )
    (net (code "106") (name "unconnected-(R50-Pad2)") (class "Default")
      (node (ref "R50") (pin "2") (pinfunction "2_2") (pintype "passive"))
    )
    (net (code "107") (name "unconnected-(R51-Pad1)") (class "Default")
      (node (ref "R51") (pin "1") (pinfunction "1_1") (pintype "passive"))
    )
    (net (code "108") (name "unconnected-(R51-Pad2)") (class "Default")
      (node (ref "R51") (pin "2") (pinfunction "2_2") (pintype "passive"))
    )
    (net (code "109") (name "unconnected-(R52-Pad1)") (class "Default")
      (node (ref "R52") (pin "1") (pinfunction "1_1") (pintype "passive"))
    )
    (net (code "110") (name "unconnected-(R52-Pad2)") (class "Default")
      (node (ref "R52") (pin "2") (pinfunction "2_2") (pintype "passive"))
    )
    (net (code "111") (name "unconnected-(R53-Pad1)") (class "Default")
      (node (ref "R53") (pin "1") (pinfunction "1_1") (pintype "passive"))
    )
    (net (code "112") (name "unconnected-(R53-Pad2)") (class "Default")
      (node (ref "R53") (pin "2") (pinfunction "2_2") (pintype "passive"))
    )
    (net (code "113") (name "unconnected-(R54-Pad1)") (class "Default")
      (node (ref "R54") (pin "1") (pinfunction "1_1") (pintype "passive"))
    )
    (net (code "114") (name "unconnected-(R54-Pad2)") (class "Default")
      (node (ref "R54") (pin "2") (pinfunction "2_2") (pintype "passive"))
    )
    (net (code "115") (name "unconnected-(R55-Pad1)") (class "Default")
      (node (ref "R55") (pin "1") (pinfunction "1_1") (pintype "passive"))
    )
    (net (code "116") (name "unconnected-(R55-Pad2)") (class "Default")
      (node (ref "R55") (pin "2") (pinfunction "2_2") (pintype "passive"))
    )
    (net (code "117") (name "unconnected-(R56-Pad1)") (class "Default")
      (node (ref "R56") (pin "1") (pinfunction "1_1") (pintype "passive"))
    )
    (net (code "118") (name "unconnected-(R56-Pad2)") (class "Default")
      (node (ref "R56") (pin "2") (pinfunction "2_2") (pintype "passive"))
    )
    (net (code "119") (name "unconnected-(R57-Pad1)") (class "Default")
      (node (ref "R57") (pin "1") (pinfunction "1_1") (pintype "passive"))
    )
    (net (code "120") (name "unconnected-(R57-Pad2)") (class "Default")
      (node (ref "R57") (pin "2") (pinfunction "2_2") (pintype "passive"))
    )
    (net (code "121") (name "unconnected-(R58-Pad1)") (class "Default")
      (node (ref "R58") (pin "1") (pinfunction "1_1") (pintype "passive"))
    )
    (net (code "122") (name "unconnected-(R58-Pad2)") (class "Default")
      (node (ref "R58") (pin "2") (pinfunction "2_2") (pintype "passive"))
    )
    (net (code "123") (name "unconnected-(R59-Pad1)") (class "Default")
      (node (ref "R59") (pin "1") (pinfunction "1_1") (pintype "passive"))
    )
    (net (code "124") (name "unconnected-(R59-Pad2)") (class "Default")
      (node (ref "R59") (pin "2") (pinfunction "2_2") (pintype "passive"))
    )
    (net (code "125") (name "unconnected-(R60-Pad1)") (class "Default")
      (node (ref "R60") (pin "1") (pinfunction "1_1") (pintype "passive"))
    )
    (net (code "126") (name "unconnected-(R60-Pad2)") (class "Default")
      (node (ref "R60") (pin "2") (pinfunction "2_2") (pintype "passive"))
    )
    (net (code "127") (name "unconnected-(R61-Pad1)") (class "Default")
      (node (ref "R61") (pin "1") (pinfunction "1_1") (pintype "passive"))
    )
    (net (code "128") (name "unconnected-(R61-Pad2)") (class "Default")
      (node (ref "R61") (pin "2") (pinfunction "2_2") (pintype "passive"))
    )
    (net (code "129") (name "unconnected-(R62-Pad1)") (class "Default")
      (node (ref "R62") (pin "1") (pinfunction "1_1") (pintype "passive"))
    )
    (net (code "130") (name "unconnected-(R62-Pad2)") (class "Default")
      (node (ref "R62") (pin "2") (pinfunction "2_2") (pintype "passive"))
    )
    (net (code "131") (name "unconnected-(R63-Pad1)") (class "Default")
      (node (ref "R63") (pin "1") (pinfunction "1_1") (pintype "passive"))
    )
    (net (code "132") (name "unconnected-(R63-Pad2)") (class "Default")
      (node (ref "R63") (pin "2") (pinfunction "2_2") (pintype "passive"))
    )
    (net (code "133") (name "unconnected-(R64-Pad1)") (class "Default")
      (node (ref "R64") (pin "1") (pinfunction "1_1") (pintype "passive"))
    )
    (net (code "134") (name "unconnected-(R64-Pad2)") (class "Default")
      (node (ref "R64") (pin "2") (pinfunction "2_2") (pintype "passive"))
    )
    (net (code "135") (name "unconnected-(R65-Pad1)") (class "Default")
      (node (ref "R65") (pin "1") (pinfunction "1_1") (pintype "passive"))
    )
    (net (code "136") (name "unconnected-(R65-Pad2)") (class "Default")
      (node (ref "R65") (pin "2") (pinfunction "2_2") (pintype "passive"))
    )
    (net (code "137") (name "unconnected-(R66-Pad1)") (class "Default")
      (node (ref "R66") (pin "1") (pinfunction "1_1") (pintype "passive"))
    )
    (net (code "138") (name "unconnected-(R66-Pad2)") (class "Default")
      (node (ref "R66") (pin "2") (pinfunction "2_2") (pintype "passive"))
    )
    (net (code "139") (name "unconnected-(R67-Pad1)") (class "Default")
      (node (ref "R67") (pin "1") (pinfunction "1_1") (pintype "passive"))
    )
    (net (code "140") (name "unconnected-(R67-Pad2)") (class "Default")
      (node (ref "R67") (pin "2") (pinfunction "2_2") (pintype "passive"))
    )
    (net (code "141") (name "unconnected-(R68-Pad1)") (class "Default")
      (node (ref "R68") (pin "1") (pinfunction "1_1") (pintype "passive"))
    )
    (net (code "142") (name "unconnected-(R68-Pad2)") (class "Default")
      (node (ref "R68") (pin "2") (pinfunction "2_2") (pintype "passive"))
    )
    (net (code "143") (name "unconnected-(R69-Pad1)") (class "Default")
      (node (ref "R69") (pin "1") (pinfunction "1_1") (pintype "passive"))
    )
    (net (code "144") (name "unconnected-(R69-Pad2)") (class "Default")
      (node (ref "R69") (pin "2") (pinfunction "2_2") (pintype "passive"))
    )
    (net (code "145") (name "unconnected-(R70-Pad1)") (class "Default")
      (node (ref "R70") (pin "1") (pinfunction "1_1") (pintype "passive"))
    )
    (net (code "146") (name "unconnected-(R70-Pad2)") (class "Default")
      (node (ref "R70") (pin "2") (pinfunction "2_2") (pintype "passive"))
    )
    (net (code "147") (name "unconnected-(R71-Pad1)") (class "Default")
      (node (ref "R71") (pin "1") (pinfunction "1_1") (pintype "passive"))
    )
    (net (code "148") (name "unconnected-(R71-Pad2)") (class "Default")
      (node (ref "R71") (pin "2") (pinfunction "2_2") (pintype "passive"))
    )
    (net (code "149") (name "unconnected-(R72-Pad1)") (class "Default")
      (node (ref "R72") (pin "1") (pinfunction "1_1") (pintype "passive"))
    )
    (net (code "150") (name "unconnected-(R72-Pad2)") (class "Default")
      (node (ref "R72") (pin "2") (pinfunction "2_2") (pintype "passive"))
    )
    (net (code "151") (name "unconnected-(R73-Pad1)") (class "Default")
      (node (ref "R73") (pin "1") (pinfunction "1_1") (pintype "passive"))
    )
    (net (code "152") (name "unconnected-(R73-Pad2)") (class "Default")
      (node (ref "R73") (pin "2") (pinfunction "2_2") (pintype "passive"))
    )
    (net (code "153") (name "unconnected-(R74-Pad1)") (class "Default")
      (node (ref "R74") (pin "1") (pinfunction "1_1") (pintype "passive"))
    )
    (net (code "154") (name "unconnected-(R74-Pad2)") (class "Default")
      (node (ref "R74") (pin "2") (pinfunction "2_2") (pintype "passive"))
    )
    (net (code "155") (name "unconnected-(R75-Pad1)") (class "Default")
      (node (ref "R75") (pin "1") (pinfunction "1_1") (pintype "passive"))
    )
    (net (code "156") (name "unconnected-(R75-Pad2)") (class "Default")
      (node (ref "R75") (pin "2") (pinfunction "2_2") (pintype "passive"))
    )
    (net (code "157") (name "unconnected-(R76-Pad1)") (class "Default")
      (node (ref "R76") (pin "1") (pinfunction "1_1") (pintype "passive"))
    )
    (net (code "158") (name "unconnected-(R76-Pad2)") (class "Default")
      (node (ref "R76") (pin "2") (pinfunction "2_2") (pintype "passive"))
    )
    (net (code "159") (name "unconnected-(R77-Pad1)") (class "Default")
      (node (ref "R77") (pin "1") (pinfunction "1_1") (pintype "passive"))
    )
    (net (code "160") (name "unconnected-(R77-Pad2)") (class "Default")
      (node (ref "R77") (pin "2") (pinfunction "2_2") (pintype "passive"))
    )
    (net (code "161") (name "unconnected-(R78-Pad1)") (class "Default")
      (node (ref "R78") (pin "1") (pinfunction "1_1") (pintype "passive"))
    )
    (net (code "162") (name "unconnected-(R78-Pad2)") (class "Default")
      (node (ref "R78") (pin "2") (pinfunction "2_2") (pintype "passive"))
    )
    (net (code "163") (name "unconnected-(R79-Pad1)") (class "Default")
      (node (ref "R79") (pin "1") (pinfunction "1_1") (pintype "passive"))
    )
    (net (code "164") (name "unconnected-(R79-Pad2)") (class "Default")
      (node (ref "R79") (pin "2") (pinfunction "2_2") (pintype "passive"))
    )
    (net (code "165") (name "unconnected-(R80-Pad1)") (class "Default")
      (node (ref "R80") (pin "1") (pinfunction "1_1") (pintype "passive"))
    )
    (net (code "166") (name "unconnected-(R80-Pad2)") (class "Default")
      (node (ref "R80") (pin "2") (pinfunction "2_2") (pintype "passive"))
    )
    (net (code "167") (name "unconnected-(R81-Pad1)") (class "Default")
      (node (ref "R81") (pin "1") (pinfunction "1_1") (pintype "passive"))
    )
    (net (code "168") (name "unconnected-(R81-Pad2)") (class "Default")
      (node (ref "R81") (pin "2") (pinfunction "2_2") (pintype "passive"))
    )
    (net (code "169") (name "unconnected-(R82-Pad1)") (class "Default")
      (node (ref "R82") (pin "1") (pinfunction "1_1") (pintype "passive"))
    )
    (net (code "170") (name "unconnected-(R82-Pad2)") (class "Default")
      (node (ref "R82") (pin "2") (pinfunction "2_2") (pintype "passive"))
    )
    (net (code "171") (name "unconnected-(R83-Pad1)") (class "Default")
      (node (ref "R83") (pin "1") (pinfunction "1_1") (pintype "passive"))
    )
    (net (code "172") (name "unconnected-(R83-Pad2)") (class "Default")
      (node (ref "R83") (pin "2") (pinfunction "2_2") (pintype "passive"))
    )
    (net (code "173") (name "unconnected-(R84-Pad1)") (class "Default")
      (node (ref "R84") (pin "1") (pinfunction "1_1") (pintype "passive"))
    )
    (net (code "174") (name "unconnected-(R84-Pad2)") (class "Default")
      (node (ref "R84") (pin "2") (pinfunction "2_2") (pintype "passive"))
    )
    (net (code "175") (name "unconnected-(R85-Pad1)") (class "Default")
      (node (ref "R85") (pin "1") (pinfunction "1_1") (pintype "passive"))
    )
    (net (code "176") (name "unconnected-(R85-Pad2)") (class "Default")
      (node (ref "R85") (pin "2") (pinfunction "2_2") (pintype "passive"))
    )
    (net (code "177") (name "unconnected-(R86-Pad1)") (class "Default")
      (node (ref "R86") (pin "1") (pinfunction "1_1") (pintype "passive"))
    )
    (net (code "178") (name "unconnected-(R86-Pad2)") (class "Default")
      (node (ref "R86") (pin "2") (pinfunction "2_2") (pintype "passive"))
    )
    (net (code "179") (name "unconnected-(R87-Pad1)") (class "Default")
      (node (ref "R87") (pin "1") (pinfunction "1_1") (pintype "passive"))
    )
    (net (code "180") (name "unconnected-(R87-Pad2)") (class "Default")
      (node (ref "R87") (pin "2") (pinfunction "2_2") (pintype "passive"))
    )
    (net (code "181") (name "unconnected-(R88-Pad1)") (class "Default")
      (node (ref "R88") (pin "1") (pinfunction "1_1") (pintype "passive"))
    )
    (net (code "182") (name "unconnected-(R88-Pad2)") (class "Default")
      (node (ref "R88") (pin "2") (pinfunction "2_2") (pintype "passive"))
    )
    (net (code "183") (name "unconnected-(R89-Pad1)") (class "Default")
      (node (ref "R89") (pin "1") (pinfunction "1_1") (pintype "passive"))
    )
    (net (code "184") (name "unconnected-(R89-Pad2)") (class "Default")
      (node (ref "R89") (pin "2") (pinfunction "2_2") (pintype "passive"))
    )
    (net (code "185") (name "unconnected-(R90-Pad1)") (class "Default")
      (node (ref "R90") (pin "1") (pinfunction "1_1") (pintype "passive"))
    )
    (net (code "186") (name "unconnected-(R90-Pad2)") (class "Default")
      (node (ref "R90") (pin "2") (pinfunction "2_2") (pintype "passive"))
    )
    (net (code "187") (name "unconnected-(R91-Pad1)") (class "Default")
      (node (ref "R91") (pin "1") (pinfunction "1_1") (pintype "passive"))
    )
    (net (code "188") (name "unconnected-(R91-Pad2)") (class "Default")
      (node (ref "R91") (pin "2") (pinfunction "2_2") (pintype "passive"))
    )
    (net (code "189") (name "unconnected-(R92-Pad1)") (class "Default")
      (node (ref "R92") (pin "1") (pinfunction "1_1") (pintype "passive"))
    )
    (net (code "190") (name "unconnected-(R92-Pad2)") (class "Default")
      (node (ref "R92") (pin "2") (pinfunction "2_2") (pintype "passive"))
    )
    (net (code "191") (name "unconnected-(R93-Pad1)") (class "Default")
      (node (ref "R93") (pin "1") (pinfunction "1_1") (pintype "passive"))
    )
    (net (code "192") (name "unconnected-(R93-Pad2)") (class "Default")
      (node (ref "R93") (pin "2") (pinfunction "2_2") (pintype "passive"))
    )
    (net (code "193") (name "unconnected-(R94-Pad1)") (class "Default")
      (node (ref "R94") (pin "1") (pinfunction "1_1") (pintype "passive"))
    )
    (net (code "194") (name "unconnected-(R94-Pad2)") (class "Default")
      (node (ref "R94") (pin "2") (pinfunction "2_2") (pintype "passive"))
    )
    (net (code "195") (name "unconnected-(R95-Pad1)") (class "Default")
      (node (ref "R95") (pin "1") (pinfunction "1_1") (pintype "passive"))
    )
    (net (code "196") (name "unconnected-(R95-Pad2)") (class "Default")
      (node (ref "R95") (pin "2") (pinfunction "2_2") (pintype "passive"))
    )
    (net (code "197") (name "unconnected-(R96-Pad1)") (class "Default")
      (node (ref "R96") (pin "1") (pinfunction "1_1") (pintype "passive"))
    )
    (net (code "198") (name "unconnected-(R96-Pad2)") (class "Default")
      (node (ref "R96") (pin "2") (pinfunction "2_2") (pintype "passive"))
    )
    (net (code "199") (name "unconnected-(R97-Pad1)") (class "Default")
      (node (ref "R97") (pin "1") (pinfunction "1_1") (pintype "passive"))
    )
    (net (code "200") (name "unconnected-(R97-Pad2)") (class "Default")
      (node (ref "R97") (pin "2") (pinfunction "2_2") (pintype "passive"))
    )
    (net (code "201") (name "unconnected-(R98-Pad1)") (class "Default")
      (node (ref "R98") (pin "1") (pinfunction "1_1") (pintype "passive"))
    )
    (net (code "202") (name "unconnected-(R98-Pad2)") (class "Default")
      (node (ref "R98") (pin "2") (pinfunction "2_2") (pintype "passive"))
    )
    (net (code "203") (name "unconnected-(R99-Pad1)") (class "Default")
      (node (ref "R99") (pin "1") (pinfunction "1_1") (pintype "passive"))
    )
    (net (code "204") (name "unconnected-(R99-Pad2)") (class "Default")
      (node (ref "R99") (pin "2") (pinfunction "2_2") (pintype "passive"))
    )
    (net (code "205") (name "unconnected-(R100-Pad1)") (class "Default")
      (node (ref "R100") (pin "1") (pinfunction "1_1") (pintype "passive"))
    )
    (net (code "206") (name "unconnected-(R100-Pad2)") (class "Default")
      (node (ref "R100") (pin "2") (pinfunction "2_2") (pintype "passive"))
    )
    (net (code "207") (name "unconnected-(U$19-EN-PadP$9)") (class "Default")
      (node (ref "U$19") (pin "P$9") (pinfunction "EN_P$9") (pintype "bidirectional"))
    )
    (net (code "208") (name "unconnected-(U$19-NC-PadP$6)") (class "Default")
      (node (ref "U$19") (pin "P$6") (pinfunction "NC_P$6") (pintype "bidirectional"))
    )
    (net (code "209") (name "unconnected-(U$19-NC1-PadP$7)") (class "Default")
      (node (ref "U$19") (pin "P$7") (pinfunction "NC1_P$7") (pintype "bidirectional"))
    )
    (net (code "210") (name "unconnected-(U$19-PG-PadP$8)") (class "Default")
      (node (ref "U$19") (pin "P$8") (pinfunction "PG_P$8") (pintype "bidirectional"))
    )
  )
)
